# Relay_5VDC.net
KiCad netlist of a schematic drawn in Altium Designer
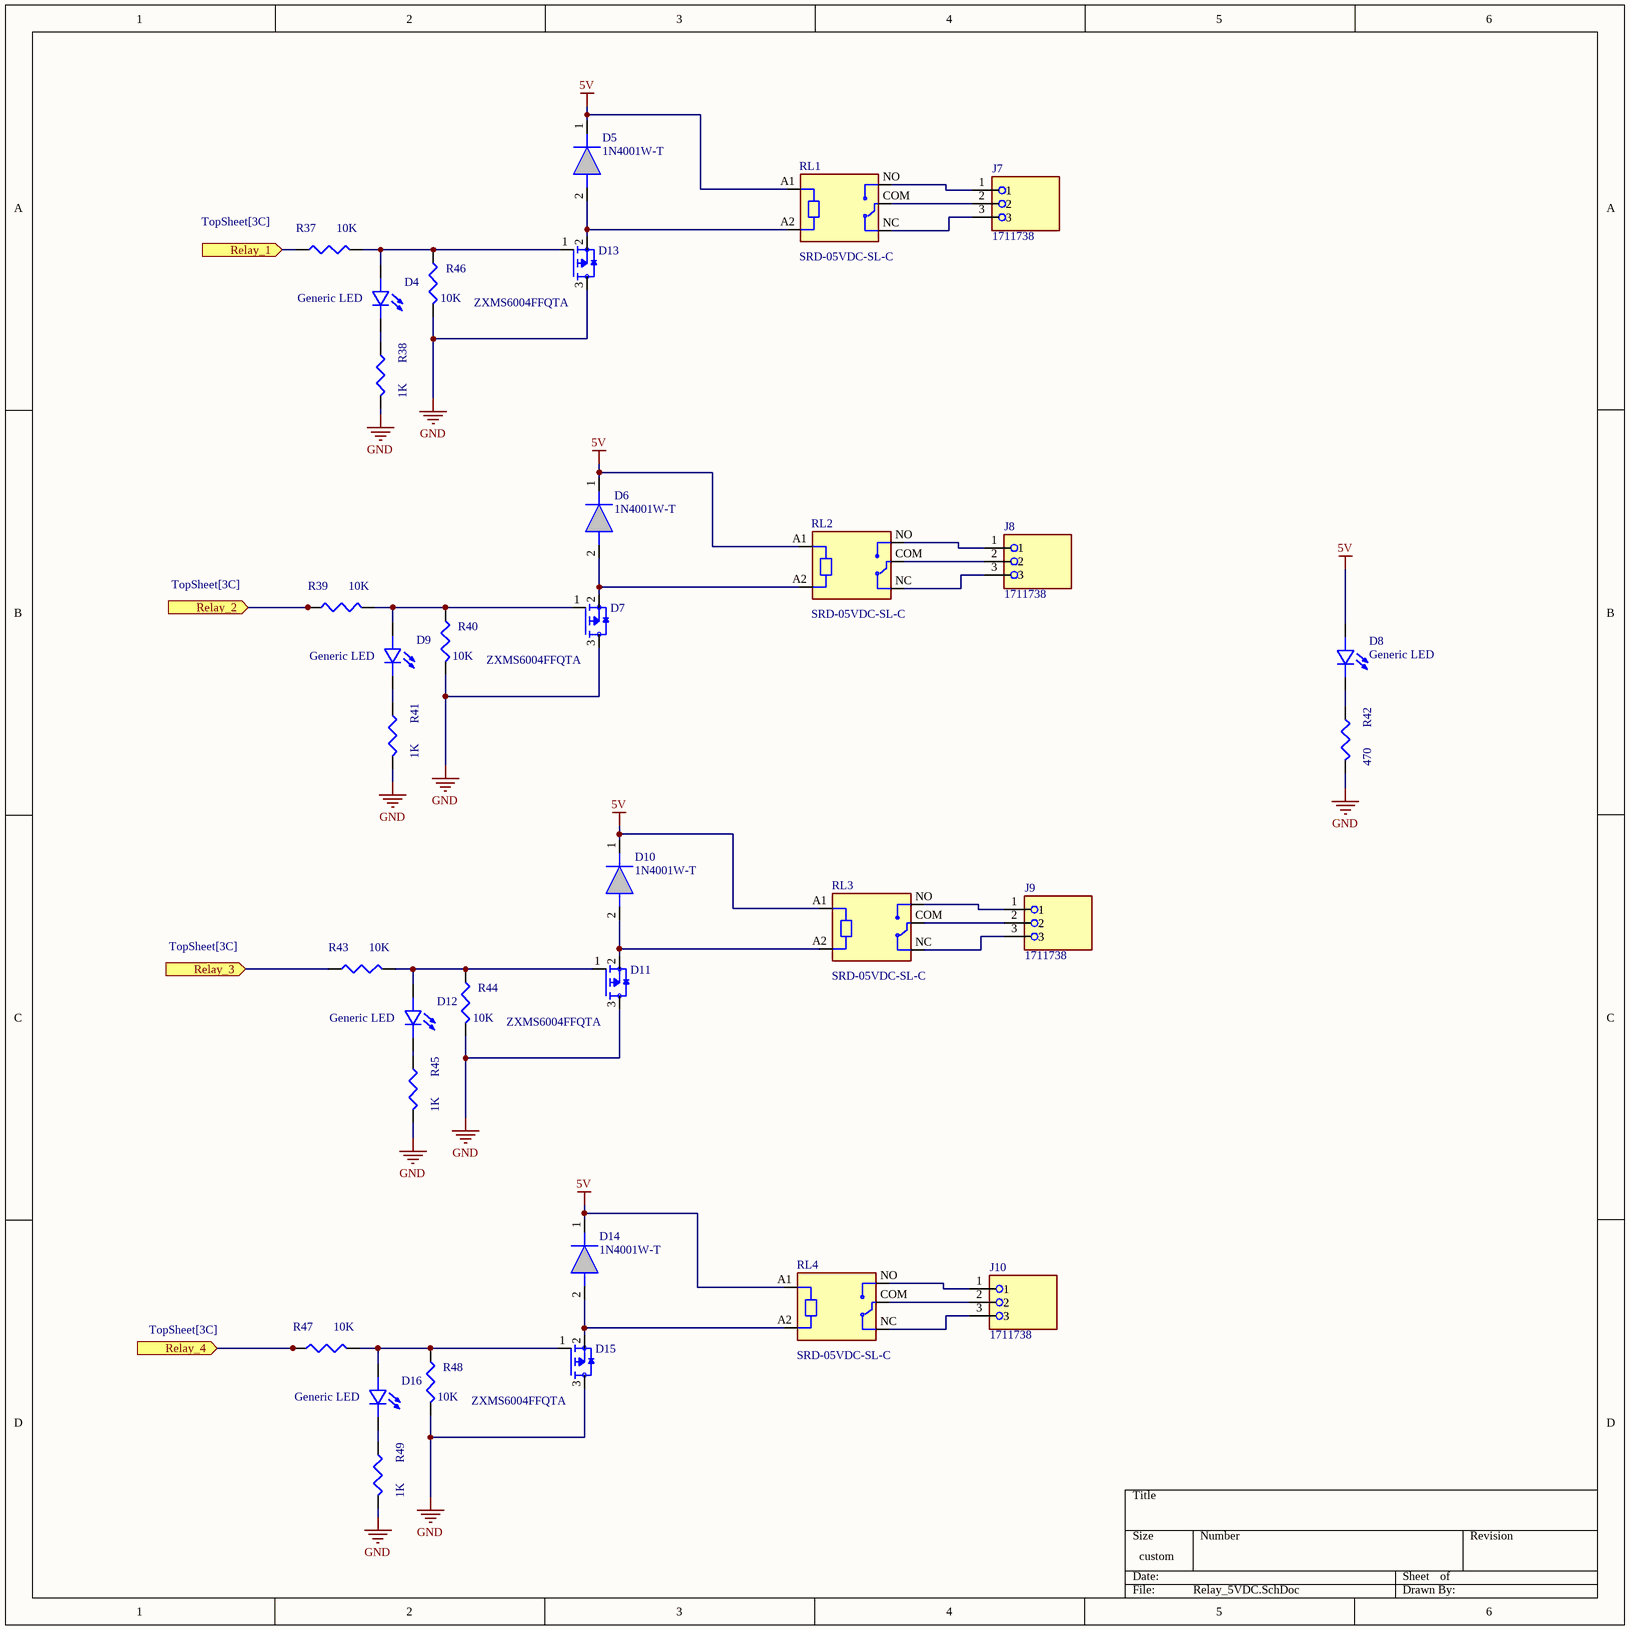
[diagram p0: Relay_5VDC.SchDoc]

(export (version "E")
  (design (tool "Eeschema 10.0.6"))
  (components
    (comp (ref "D4")
      (value "Generic LED")
      (footprint "0603D-B")
      (description "Generic LED SMD")
      (fields (field (name "MF") "Osram") (field (name "MP") "LHN974 RED LED 1206"))
      (libsource (lib "common component") (part "LED"))
    )
    (comp (ref "D5")
      (value "1N4001W-T")
      (footprint "SODFL3818X130N")
      (description "Rectifiers SOD-123,1A,50V,GP")
      (fields (field (name "MOUSER PART NUMBER") "583-1N4001W-T"))
      (libsource (lib "1N4001W-T") (part "1N4001W-T"))
    )
    (comp (ref "D6")
      (value "1N4001W-T")
      (footprint "SODFL3818X130N")
      (description "Rectifiers SOD-123,1A,50V,GP")
      (fields (field (name "MOUSER PART NUMBER") "583-1N4001W-T"))
      (libsource (lib "1N4001W-T") (part "1N4001W-T"))
    )
    (comp (ref "D7")
      (value "ZXMS6004FFQTA")
      (footprint "SOT95P240X100-3N")
      (libsource (lib "ZXMS6004FFQTA") (part "ZXMS6004FFQTA"))
    )
    (comp (ref "D8")
      (value "Generic LED")
      (footprint "0603D-B")
      (description "Generic LED SMD")
      (fields (field (name "MF") "Osram") (field (name "MP") "LHN974 RED LED 1206"))
      (libsource (lib "common component") (part "LED"))
    )
    (comp (ref "D9")
      (value "Generic LED")
      (footprint "0603D-B")
      (description "Generic LED SMD")
      (fields (field (name "MF") "Osram") (field (name "MP") "LHN974 RED LED 1206"))
      (libsource (lib "common component") (part "LED"))
    )
    (comp (ref "D10")
      (value "1N4001W-T")
      (footprint "SODFL3818X130N")
      (description "Rectifiers SOD-123,1A,50V,GP")
      (fields (field (name "MOUSER PART NUMBER") "583-1N4001W-T"))
      (libsource (lib "1N4001W-T") (part "1N4001W-T"))
    )
    (comp (ref "D11")
      (value "ZXMS6004FFQTA")
      (footprint "SOT95P240X100-3N")
      (libsource (lib "ZXMS6004FFQTA") (part "ZXMS6004FFQTA"))
    )
    (comp (ref "D12")
      (value "Generic LED")
      (footprint "0603D-B")
      (description "Generic LED SMD")
      (fields (field (name "MF") "Osram") (field (name "MP") "LHN974 RED LED 1206"))
      (libsource (lib "common component") (part "LED"))
    )
    (comp (ref "D13")
      (value "ZXMS6004FFQTA")
      (footprint "SOT95P240X100-3N")
      (libsource (lib "ZXMS6004FFQTA") (part "ZXMS6004FFQTA"))
    )
    (comp (ref "D14")
      (value "1N4001W-T")
      (footprint "SODFL3818X130N")
      (description "Rectifiers SOD-123,1A,50V,GP")
      (fields (field (name "MOUSER PART NUMBER") "583-1N4001W-T"))
      (libsource (lib "1N4001W-T") (part "1N4001W-T"))
    )
    (comp (ref "D15")
      (value "ZXMS6004FFQTA")
      (footprint "SOT95P240X100-3N")
      (libsource (lib "ZXMS6004FFQTA") (part "ZXMS6004FFQTA"))
    )
    (comp (ref "D16")
      (value "Generic LED")
      (footprint "0603D-B")
      (description "Generic LED SMD")
      (fields (field (name "MF") "Osram") (field (name "MP") "LHN974 RED LED 1206"))
      (libsource (lib "common component") (part "LED"))
    )
    (comp (ref "J7")
      (value "1711738")
      (footprint "1711738")
      (description "PCB Terminal Screw 5.08mm 12AWG 400V 24A 3 Position COMBICON MKDS Series ¦ Phoenix Contact 1711738")
      (libsource (lib "1711738") (part "1711738"))
    )
    (comp (ref "J8")
      (value "1711738")
      (footprint "1711738")
      (description "PCB Terminal Screw 5.08mm 12AWG 400V 24A 3 Position COMBICON MKDS Series ¦ Phoenix Contact 1711738")
      (libsource (lib "1711738") (part "1711738"))
    )
    (comp (ref "J9")
      (value "1711738")
      (footprint "1711738")
      (description "PCB Terminal Screw 5.08mm 12AWG 400V 24A 3 Position COMBICON MKDS Series ¦ Phoenix Contact 1711738")
      (libsource (lib "1711738") (part "1711738"))
    )
    (comp (ref "J10")
      (value "1711738")
      (footprint "1711738")
      (description "PCB Terminal Screw 5.08mm 12AWG 400V 24A 3 Position COMBICON MKDS Series ¦ Phoenix Contact 1711738")
      (libsource (lib "1711738") (part "1711738"))
    )
    (comp (ref "R37")
      (value "10K")
      (footprint "R0805")
      (libsource (lib "common component") (part "Resistor"))
    )
    (comp (ref "R38") (value "1K") (footprint "R0805") (libsource (lib "common component") (part "Resistor")))
    (comp (ref "R39")
      (value "10K")
      (footprint "R0805")
      (libsource (lib "common component") (part "Resistor"))
    )
    (comp (ref "R40")
      (value "10K")
      (footprint "R0805")
      (libsource (lib "common component") (part "Resistor"))
    )
    (comp (ref "R41") (value "1K") (footprint "R0805") (libsource (lib "common component") (part "Resistor")))
    (comp (ref "R42")
      (value "470")
      (footprint "R0603")
      (libsource (lib "common component") (part "Resistor"))
    )
    (comp (ref "R43")
      (value "10K")
      (footprint "R0805")
      (libsource (lib "common component") (part "Resistor"))
    )
    (comp (ref "R44")
      (value "10K")
      (footprint "R0805")
      (libsource (lib "common component") (part "Resistor"))
    )
    (comp (ref "R45") (value "1K") (footprint "R0805") (libsource (lib "common component") (part "Resistor")))
    (comp (ref "R46")
      (value "10K")
      (footprint "R0805")
      (libsource (lib "common component") (part "Resistor"))
    )
    (comp (ref "R47")
      (value "10K")
      (footprint "R0805")
      (libsource (lib "common component") (part "Resistor"))
    )
    (comp (ref "R48")
      (value "10K")
      (footprint "R0805")
      (libsource (lib "common component") (part "Resistor"))
    )
    (comp (ref "R49") (value "1K") (footprint "R0805") (libsource (lib "common component") (part "Resistor")))
    (comp (ref "RL1")
      (value "SRD-05VDC-SL-C")
      (footprint "SRD-05VDC-SL-C")
      (libsource (lib "SRD-05VDC-SL-C") (part "SRD-05VDC-SL-C"))
    )
    (comp (ref "RL2")
      (value "SRD-05VDC-SL-C")
      (footprint "SRD-05VDC-SL-C")
      (libsource (lib "SRD-05VDC-SL-C") (part "SRD-05VDC-SL-C"))
    )
    (comp (ref "RL3")
      (value "SRD-05VDC-SL-C")
      (footprint "SRD-05VDC-SL-C")
      (libsource (lib "SRD-05VDC-SL-C") (part "SRD-05VDC-SL-C"))
    )
    (comp (ref "RL4")
      (value "SRD-05VDC-SL-C")
      (footprint "SRD-05VDC-SL-C")
      (libsource (lib "SRD-05VDC-SL-C") (part "SRD-05VDC-SL-C"))
    )
  )
  (nets
    (net (code "1") (name "/Relay_1") (class "Default")
      (node (ref "R37") (pin "1") (pinfunction "1_1") (pintype "passive"))
    )
    (net (code "2") (name "/Relay_2") (class "Default")
      (node (ref "R39") (pin "1") (pinfunction "1_1") (pintype "passive"))
    )
    (net (code "3") (name "/Relay_3") (class "Default")
      (node (ref "R43") (pin "1") (pinfunction "1_1") (pintype "passive"))
    )
    (net (code "4") (name "/Relay_4") (class "Default")
      (node (ref "R47") (pin "1") (pinfunction "1_1") (pintype "passive"))
    )
    (net (code "5") (name "5V") (class "Default")
      (node (ref "D10") (pin "1") (pinfunction "K_1") (pintype "passive"))
      (node (ref "D14") (pin "1") (pinfunction "K_1") (pintype "passive"))
      (node (ref "D5") (pin "1") (pinfunction "K_1") (pintype "passive"))
      (node (ref "D6") (pin "1") (pinfunction "K_1") (pintype "passive"))
      (node (ref "D8") (pin "1") (pinfunction "POS_1") (pintype "passive"))
      (node (ref "RL1") (pin "A1") (pinfunction "A1_A1") (pintype "passive"))
      (node (ref "RL2") (pin "A1") (pinfunction "A1_A1") (pintype "passive"))
      (node (ref "RL3") (pin "A1") (pinfunction "A1_A1") (pintype "passive"))
      (node (ref "RL4") (pin "A1") (pinfunction "A1_A1") (pintype "passive"))
    )
    (net (code "6") (name "GND") (class "Default")
      (node (ref "D11") (pin "3") (pinfunction "D_3") (pintype "passive"))
      (node (ref "D13") (pin "3") (pinfunction "D_3") (pintype "passive"))
      (node (ref "D15") (pin "3") (pinfunction "D_3") (pintype "passive"))
      (node (ref "D7") (pin "3") (pinfunction "D_3") (pintype "passive"))
      (node (ref "R38") (pin "2") (pinfunction "2_2") (pintype "passive"))
      (node (ref "R40") (pin "2") (pinfunction "2_2") (pintype "passive"))
      (node (ref "R41") (pin "2") (pinfunction "2_2") (pintype "passive"))
      (node (ref "R42") (pin "2") (pinfunction "2_2") (pintype "passive"))
      (node (ref "R44") (pin "2") (pinfunction "2_2") (pintype "passive"))
      (node (ref "R45") (pin "2") (pinfunction "2_2") (pintype "passive"))
      (node (ref "R46") (pin "2") (pinfunction "2_2") (pintype "passive"))
      (node (ref "R48") (pin "2") (pinfunction "2_2") (pintype "passive"))
      (node (ref "R49") (pin "2") (pinfunction "2_2") (pintype "passive"))
    )
    (net (code "7") (name "Net-(D4-NEG)") (class "Default")
      (node (ref "D4") (pin "2") (pinfunction "NEG_2") (pintype "passive"))
      (node (ref "R38") (pin "1") (pinfunction "1_1") (pintype "passive"))
    )
    (net (code "8") (name "Net-(D6-A)") (class "Default")
      (node (ref "D6") (pin "2") (pinfunction "A_2") (pintype "passive"))
      (node (ref "D7") (pin "2") (pinfunction "S_2") (pintype "passive"))
      (node (ref "RL2") (pin "A2") (pinfunction "A2_A2") (pintype "passive"))
    )
    (net (code "9") (name "Net-(D7-G)") (class "Default")
      (node (ref "D7") (pin "1") (pinfunction "G_1") (pintype "passive"))
      (node (ref "D9") (pin "1") (pinfunction "POS_1") (pintype "passive"))
      (node (ref "R39") (pin "2") (pinfunction "2_2") (pintype "passive"))
      (node (ref "R40") (pin "1") (pinfunction "1_1") (pintype "passive"))
    )
    (net (code "10") (name "Net-(D8-NEG)") (class "Default")
      (node (ref "D8") (pin "2") (pinfunction "NEG_2") (pintype "passive"))
      (node (ref "R42") (pin "1") (pinfunction "1_1") (pintype "passive"))
    )
    (net (code "11") (name "Net-(D9-NEG)") (class "Default")
      (node (ref "D9") (pin "2") (pinfunction "NEG_2") (pintype "passive"))
      (node (ref "R41") (pin "1") (pinfunction "1_1") (pintype "passive"))
    )
    (net (code "12") (name "Net-(D10-A)") (class "Default")
      (node (ref "D10") (pin "2") (pinfunction "A_2") (pintype "passive"))
      (node (ref "D11") (pin "2") (pinfunction "S_2") (pintype "passive"))
      (node (ref "RL3") (pin "A2") (pinfunction "A2_A2") (pintype "passive"))
    )
    (net (code "13") (name "Net-(D11-G)") (class "Default")
      (node (ref "D11") (pin "1") (pinfunction "G_1") (pintype "passive"))
      (node (ref "D12") (pin "1") (pinfunction "POS_1") (pintype "passive"))
      (node (ref "R43") (pin "2") (pinfunction "2_2") (pintype "passive"))
      (node (ref "R44") (pin "1") (pinfunction "1_1") (pintype "passive"))
    )
    (net (code "14") (name "Net-(D12-NEG)") (class "Default")
      (node (ref "D12") (pin "2") (pinfunction "NEG_2") (pintype "passive"))
      (node (ref "R45") (pin "1") (pinfunction "1_1") (pintype "passive"))
    )
    (net (code "15") (name "Net-(D13-G)") (class "Default")
      (node (ref "D13") (pin "1") (pinfunction "G_1") (pintype "passive"))
      (node (ref "D4") (pin "1") (pinfunction "POS_1") (pintype "passive"))
      (node (ref "R37") (pin "2") (pinfunction "2_2") (pintype "passive"))
      (node (ref "R46") (pin "1") (pinfunction "1_1") (pintype "passive"))
    )
    (net (code "16") (name "Net-(D13-S)") (class "Default")
      (node (ref "D13") (pin "2") (pinfunction "S_2") (pintype "passive"))
      (node (ref "D5") (pin "2") (pinfunction "A_2") (pintype "passive"))
      (node (ref "RL1") (pin "A2") (pinfunction "A2_A2") (pintype "passive"))
    )
    (net (code "17") (name "Net-(D14-A)") (class "Default")
      (node (ref "D14") (pin "2") (pinfunction "A_2") (pintype "passive"))
      (node (ref "D15") (pin "2") (pinfunction "S_2") (pintype "passive"))
      (node (ref "RL4") (pin "A2") (pinfunction "A2_A2") (pintype "passive"))
    )
    (net (code "18") (name "Net-(D15-G)") (class "Default")
      (node (ref "D15") (pin "1") (pinfunction "G_1") (pintype "passive"))
      (node (ref "D16") (pin "1") (pinfunction "POS_1") (pintype "passive"))
      (node (ref "R47") (pin "2") (pinfunction "2_2") (pintype "passive"))
      (node (ref "R48") (pin "1") (pinfunction "1_1") (pintype "passive"))
    )
    (net (code "19") (name "Net-(D16-NEG)") (class "Default")
      (node (ref "D16") (pin "2") (pinfunction "NEG_2") (pintype "passive"))
      (node (ref "R49") (pin "1") (pinfunction "1_1") (pintype "passive"))
    )
    (net (code "20") (name "Net-(J7-Pad1)") (class "Default")
      (node (ref "J7") (pin "1") (pinfunction "1_1") (pintype "passive"))
      (node (ref "RL1") (pin "NO") (pinfunction "NO_NO") (pintype "passive"))
    )
    (net (code "21") (name "Net-(J7-Pad2)") (class "Default")
      (node (ref "J7") (pin "2") (pinfunction "2_2") (pintype "passive"))
      (node (ref "RL1") (pin "COM") (pinfunction "COM_COM") (pintype "passive"))
    )
    (net (code "22") (name "Net-(J7-Pad3)") (class "Default")
      (node (ref "J7") (pin "3") (pinfunction "3_3") (pintype "passive"))
      (node (ref "RL1") (pin "NC") (pinfunction "NC_NC") (pintype "passive"))
    )
    (net (code "23") (name "Net-(J8-Pad1)") (class "Default")
      (node (ref "J8") (pin "1") (pinfunction "1_1") (pintype "passive"))
      (node (ref "RL2") (pin "NO") (pinfunction "NO_NO") (pintype "passive"))
    )
    (net (code "24") (name "Net-(J8-Pad2)") (class "Default")
      (node (ref "J8") (pin "2") (pinfunction "2_2") (pintype "passive"))
      (node (ref "RL2") (pin "COM") (pinfunction "COM_COM") (pintype "passive"))
    )
    (net (code "25") (name "Net-(J8-Pad3)") (class "Default")
      (node (ref "J8") (pin "3") (pinfunction "3_3") (pintype "passive"))
      (node (ref "RL2") (pin "NC") (pinfunction "NC_NC") (pintype "passive"))
    )
    (net (code "26") (name "Net-(J9-Pad1)") (class "Default")
      (node (ref "J9") (pin "1") (pinfunction "1_1") (pintype "passive"))
      (node (ref "RL3") (pin "NO") (pinfunction "NO_NO") (pintype "passive"))
    )
    (net (code "27") (name "Net-(J9-Pad2)") (class "Default")
      (node (ref "J9") (pin "2") (pinfunction "2_2") (pintype "passive"))
      (node (ref "RL3") (pin "COM") (pinfunction "COM_COM") (pintype "passive"))
    )
    (net (code "28") (name "Net-(J9-Pad3)") (class "Default")
      (node (ref "J9") (pin "3") (pinfunction "3_3") (pintype "passive"))
      (node (ref "RL3") (pin "NC") (pinfunction "NC_NC") (pintype "passive"))
    )
    (net (code "29") (name "Net-(J10-Pad1)") (class "Default")
      (node (ref "J10") (pin "1") (pinfunction "1_1") (pintype "passive"))
      (node (ref "RL4") (pin "NO") (pinfunction "NO_NO") (pintype "passive"))
    )
    (net (code "30") (name "Net-(J10-Pad2)") (class "Default")
      (node (ref "J10") (pin "2") (pinfunction "2_2") (pintype "passive"))
      (node (ref "RL4") (pin "COM") (pinfunction "COM_COM") (pintype "passive"))
    )
    (net (code "31") (name "Net-(J10-Pad3)") (class "Default")
      (node (ref "J10") (pin "3") (pinfunction "3_3") (pintype "passive"))
      (node (ref "RL4") (pin "NC") (pinfunction "NC_NC") (pintype "passive"))
    )
  )
)
